# CAMERA_DVP_FPC24_OV2640.net
KiCad netlist of a schematic drawn in Altium Designer
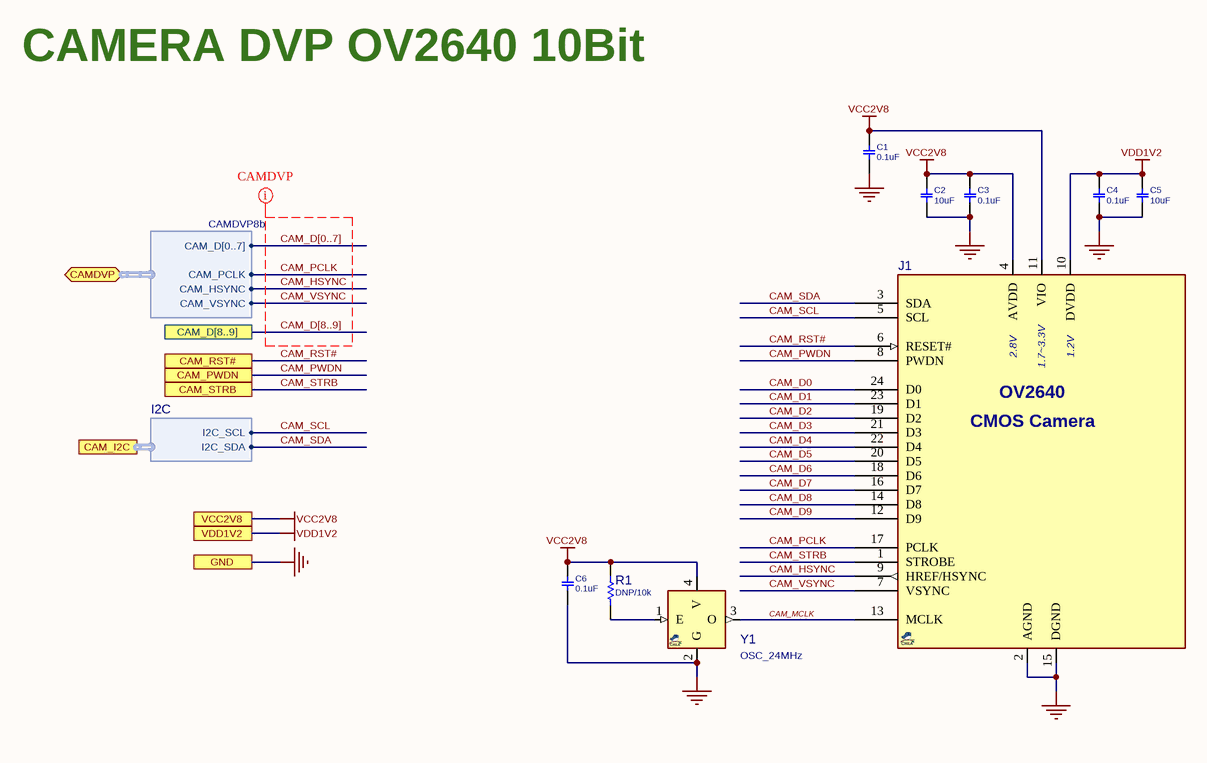
[diagram p0: CAMERA_DVP_FPC24_OV2640.SchDoc]

(export (version "E")
  (design (tool "Eeschema 10.0.6"))
  (components
    (comp (ref "C1")
      (value "0.1uF")
      (footprint "C0402")
      (description "CAP, MLCC")
      (libsource (lib "mlcc_smd_passive") (part "CAP_SMD_MLCC_100n50TDK"))
    )
    (comp (ref "C2")
      (value "10uF")
      (footprint "C0402")
      (description "CAP, MLCC")
      (libsource (lib "mlcc_smd_passive") (part "CAP_SMD_MLCC_100n50TDK"))
    )
    (comp (ref "C3")
      (value "0.1uF")
      (footprint "C0402")
      (description "CAP, MLCC")
      (libsource (lib "mlcc_smd_passive") (part "CAP_SMD_MLCC_100n50TDK"))
    )
    (comp (ref "C4")
      (value "0.1uF")
      (footprint "C0402")
      (description "CAP, MLCC")
      (libsource (lib "mlcc_smd_passive") (part "CAP_SMD_MLCC_100n50TDK"))
    )
    (comp (ref "C5")
      (value "10uF")
      (footprint "C0402")
      (description "CAP, MLCC")
      (libsource (lib "mlcc_smd_passive") (part "CAP_SMD_MLCC_100n50TDK"))
    )
    (comp (ref "C6")
      (value "0.1uF")
      (footprint "C0402")
      (description "CAP, MLCC")
      (libsource (lib "mlcc_smd_passive") (part "CAP_SMD_MLCC_100n50TDK"))
    )
    (comp (ref "J1")
      (value "OV2640")
      (footprint "FPC50_24")
      (description "Camera Module, Color CMOS 2MP, DVP FPC24")
      (libsource (lib "camera") (part "OV2640_FPC24"))
    )
    (comp (ref "R1")
      (value "DNP/10k")
      (footprint "R0402")
      (description "RESISTOR, SMD, THICK FILM, YAGEO")
      (fields (field (name "MANF_P#") "RC0402FR-071KL") (field (name "MANF") "Yageo"))
      (libsource (lib "res_smd_Yageo0402_thickfilm") (part "RES_SMD_1K_0402YK"))
    )
    (comp (ref "Y1")
      (value "OSC_24MHz")
      (footprint "XTL_4_3225GEN")
      (description "CLOCK OSCILLATOR, 25MHz, 10PPM, 3.2X2.5mm")
      (fields (field (name "MANF") "ECS") (field (name "MANF_P#") "OT322524MJBA4SL"))
      (libsource (lib "crystal_osc") (part "OSC_4_25MHz_3225E"))
    )
  )
  (nets
    (net (code "4") (name "/CAM_D0") (class "Default")
      (node (ref "J1") (pin "24") (pinfunction "D0_24") (pintype "passive"))
    )
    (net (code "5") (name "/CAM_D1") (class "Default")
      (node (ref "J1") (pin "23") (pinfunction "D1_23") (pintype "passive"))
    )
    (net (code "6") (name "/CAM_D2") (class "Default")
      (node (ref "J1") (pin "19") (pinfunction "D2_19") (pintype "passive"))
    )
    (net (code "7") (name "/CAM_D3") (class "Default")
      (node (ref "J1") (pin "21") (pinfunction "D3_21") (pintype "passive"))
    )
    (net (code "8") (name "/CAM_D4") (class "Default")
      (node (ref "J1") (pin "22") (pinfunction "D4_22") (pintype "passive"))
    )
    (net (code "9") (name "/CAM_D5") (class "Default")
      (node (ref "J1") (pin "20") (pinfunction "D5_20") (pintype "passive"))
    )
    (net (code "10") (name "/CAM_D6") (class "Default")
      (node (ref "J1") (pin "18") (pinfunction "D6_18") (pintype "passive"))
    )
    (net (code "11") (name "/CAM_D7") (class "Default")
      (node (ref "J1") (pin "16") (pinfunction "D7_16") (pintype "passive"))
    )
    (net (code "12") (name "/CAM_D8") (class "Default")
      (node (ref "J1") (pin "14") (pinfunction "D8_14") (pintype "passive"))
    )
    (net (code "13") (name "/CAM_D9") (class "Default")
      (node (ref "J1") (pin "12") (pinfunction "D9_12") (pintype "passive"))
    )
    (net (code "15") (name "/CAM_HSYNC") (class "Default")
      (node (ref "J1") (pin "9") (pinfunction "HREF/HSYNC_9") (pintype "output"))
    )
    (net (code "16") (name "/CAM_MCLK") (class "Default")
      (node (ref "J1") (pin "13") (pinfunction "MCLK_13") (pintype "passive"))
      (node (ref "Y1") (pin "3") (pinfunction "O_3") (pintype "output"))
    )
    (net (code "17") (name "/CAM_PCLK") (class "Default")
      (node (ref "J1") (pin "17") (pinfunction "PCLK_17") (pintype "passive"))
    )
    (net (code "18") (name "/CAM_PWDN") (class "Default")
      (node (ref "J1") (pin "8") (pinfunction "PWDN_8") (pintype "passive"))
    )
    (net (code "19") (name "/CAM_RST#") (class "Default")
      (node (ref "J1") (pin "6") (pinfunction "RESET#_6") (pintype "input"))
    )
    (net (code "20") (name "/CAM_SCL") (class "Default")
      (node (ref "J1") (pin "5") (pinfunction "SCL_5") (pintype "passive"))
    )
    (net (code "21") (name "/CAM_SDA") (class "Default")
      (node (ref "J1") (pin "3") (pinfunction "SDA_3") (pintype "passive"))
    )
    (net (code "22") (name "/CAM_STRB") (class "Default")
      (node (ref "J1") (pin "1") (pinfunction "STROBE_1") (pintype "passive"))
    )
    (net (code "23") (name "/CAM_VSYNC") (class "Default")
      (node (ref "J1") (pin "7") (pinfunction "VSYNC_7") (pintype "passive"))
    )
    (net (code "26") (name "GND") (class "Default")
      (node (ref "C1") (pin "2") (pinfunction "2_2") (pintype "passive"))
      (node (ref "C2") (pin "2") (pinfunction "2_2") (pintype "passive"))
      (node (ref "C3") (pin "2") (pinfunction "2_2") (pintype "passive"))
      (node (ref "C4") (pin "2") (pinfunction "2_2") (pintype "passive"))
      (node (ref "C5") (pin "2") (pinfunction "2_2") (pintype "passive"))
      (node (ref "C6") (pin "2") (pinfunction "2_2") (pintype "passive"))
      (node (ref "J1") (pin "15") (pinfunction "DGND_15") (pintype "power_in"))
      (node (ref "J1") (pin "2") (pinfunction "AGND_2") (pintype "power_in"))
      (node (ref "Y1") (pin "2") (pinfunction "G_2") (pintype "power_in"))
    )
    (net (code "27") (name "Net-(Y1-E)") (class "Default")
      (node (ref "R1") (pin "2") (pinfunction "2_2") (pintype "passive"))
      (node (ref "Y1") (pin "1") (pinfunction "E_1") (pintype "input"))
    )
    (net (code "28") (name "VCC2V8") (class "Default")
      (node (ref "C1") (pin "1") (pinfunction "1_1") (pintype "passive"))
      (node (ref "C2") (pin "1") (pinfunction "1_1") (pintype "passive"))
      (node (ref "C3") (pin "1") (pinfunction "1_1") (pintype "passive"))
      (node (ref "C6") (pin "1") (pinfunction "1_1") (pintype "passive"))
      (node (ref "J1") (pin "11") (pinfunction "VIO_11") (pintype "power_in"))
      (node (ref "J1") (pin "4") (pinfunction "AVDD_4") (pintype "power_in"))
      (node (ref "R1") (pin "1") (pinfunction "1_1") (pintype "passive"))
      (node (ref "Y1") (pin "4") (pinfunction "V_4") (pintype "power_in"))
    )
    (net (code "29") (name "VDD1V2") (class "Default")
      (node (ref "C4") (pin "1") (pinfunction "1_1") (pintype "passive"))
      (node (ref "C5") (pin "1") (pinfunction "1_1") (pintype "passive"))
      (node (ref "J1") (pin "10") (pinfunction "DVDD_10") (pintype "power_in"))
    )
  )
)
